# AdelinoR2.net
KiCad netlist of a schematic drawn in EAGLE
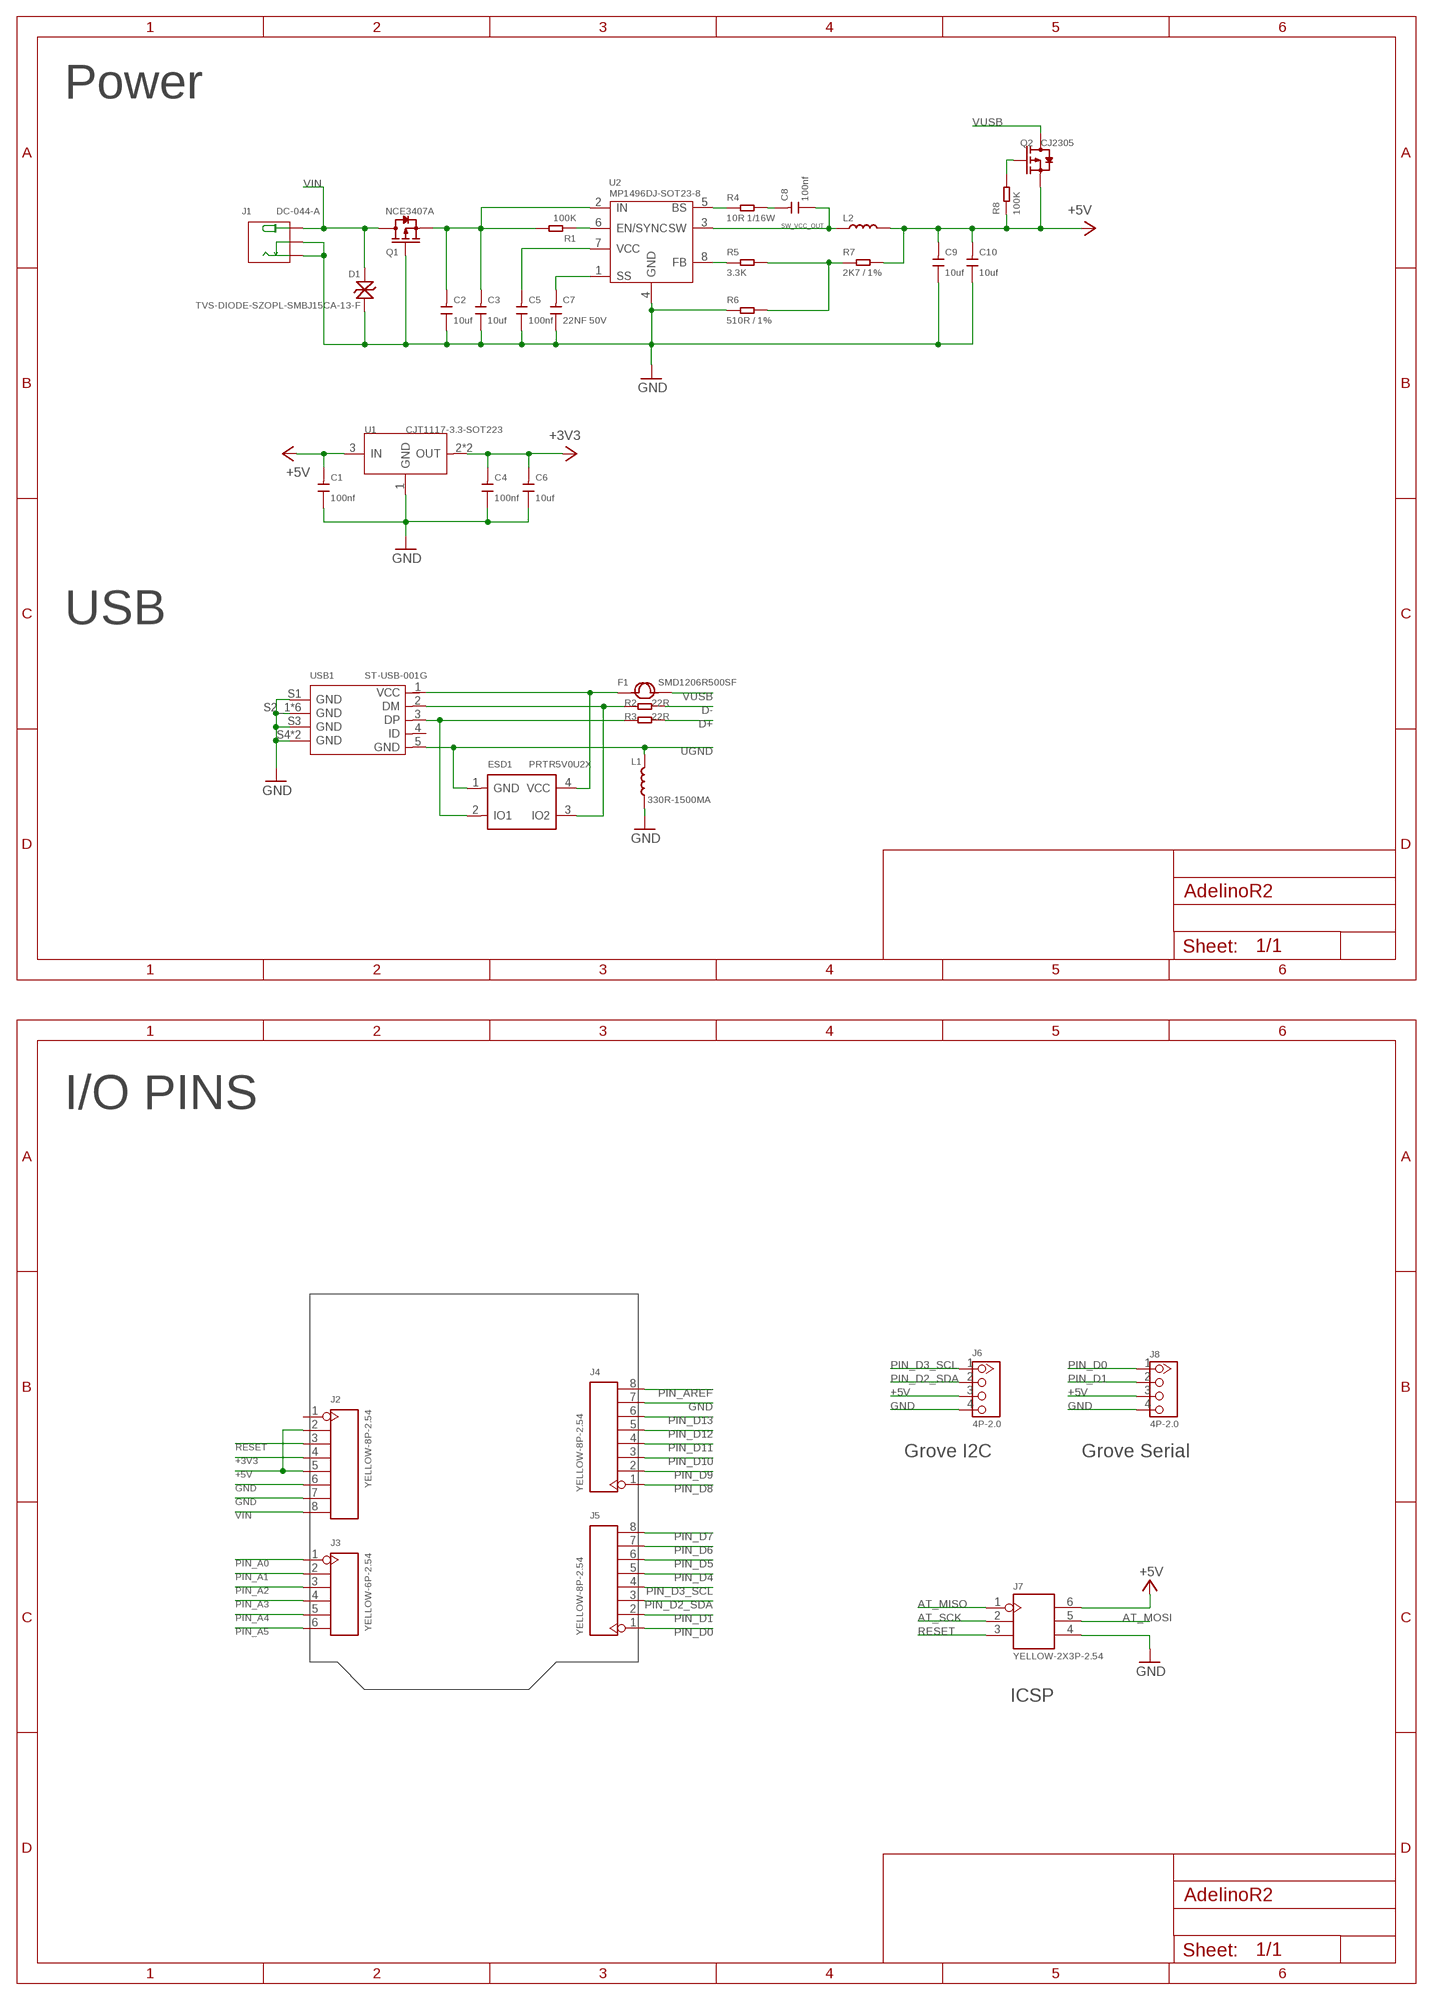
[diagram p0: schematic, sheet 1, part 1 of 2]
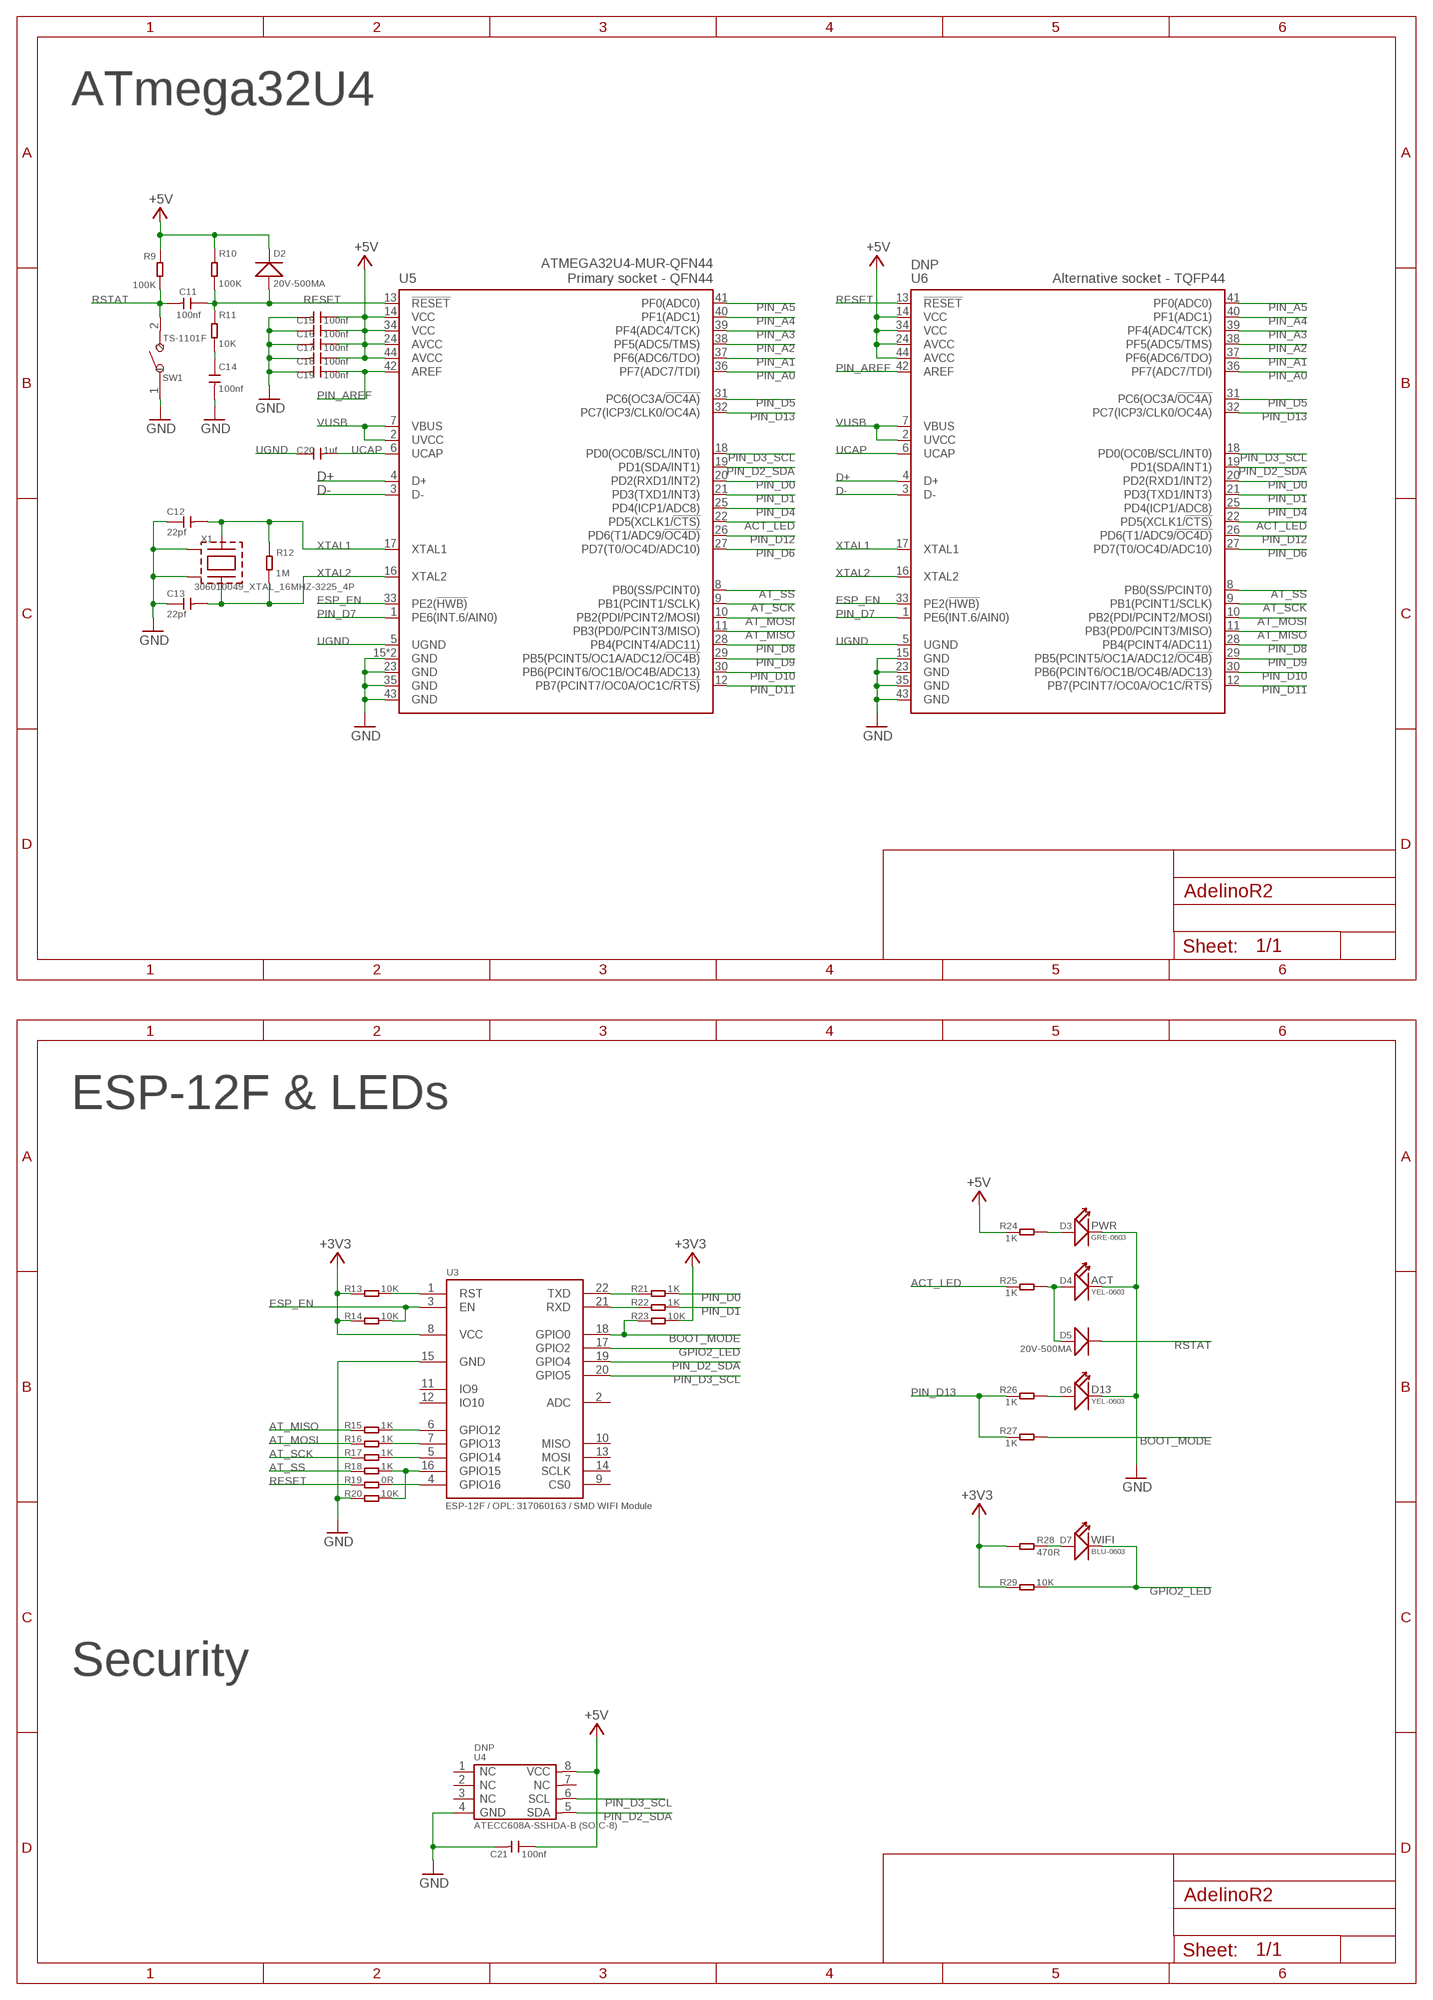
[diagram p1: schematic, sheet 1, part 2 of 2]

(export (version "E")
  (design (tool "Eeschema 10.0.6"))
  (components
    (comp (ref "C1")
      (value "100nf")
      (footprint "eagle-import:C0402")
      (fields (field (name "MPN") "CC0402KRX7R8BB104"))
      (libsource (lib "eagle-import") (part "CERAMIC-100NF-25V-10%-X7R(0402)"))
    )
    (comp (ref "C2")
      (value "10uf")
      (footprint "eagle-import:C0805")
      (fields (field (name "MPN") "CC0805KKX5R8BB106"))
      (libsource (lib "eagle-import") (part "CERAMIC-10UF-25V-10%-X5R(0805)"))
    )
    (comp (ref "C3")
      (value "10uf")
      (footprint "eagle-import:C0805")
      (fields (field (name "MPN") "CC0805KKX5R8BB106"))
      (libsource (lib "eagle-import") (part "CERAMIC-10UF-25V-10%-X5R(0805)"))
    )
    (comp (ref "C4")
      (value "100nf")
      (footprint "eagle-import:C0402")
      (fields (field (name "MPN") "CC0402KRX7R8BB104"))
      (libsource (lib "eagle-import") (part "CERAMIC-100NF-25V-10%-X7R(0402)"))
    )
    (comp (ref "C5")
      (value "100nf")
      (footprint "eagle-import:C0402")
      (fields (field (name "MPN") "CC0402KRX7R8BB104"))
      (libsource (lib "eagle-import") (part "CERAMIC-100NF-25V-10%-X7R(0402)"))
    )
    (comp (ref "C6")
      (value "10uf")
      (footprint "eagle-import:C0805")
      (fields (field (name "MPN") "CC0805KKX5R8BB106"))
      (libsource (lib "eagle-import") (part "CERAMIC-10UF-25V-10%-X5R(0805)"))
    )
    (comp (ref "C7")
      (value "22NF 50V")
      (footprint "eagle-import:C0402")
      (fields (field (name "MPN") "CC0402KRX7R9BB223"))
      (libsource (lib "eagle-import") (part "CERAMIC-22NF-50V-10%-X7R(0402)"))
    )
    (comp (ref "C8")
      (value "100nf")
      (footprint "eagle-import:C0402")
      (fields (field (name "MPN") "CC0402KRX7R8BB104"))
      (libsource (lib "eagle-import") (part "CERAMIC-100NF-25V-10%-X7R(0402)"))
    )
    (comp (ref "C9")
      (value "10uf")
      (footprint "eagle-import:C0805")
      (fields (field (name "MPN") "CC0805KKX5R8BB106"))
      (libsource (lib "eagle-import") (part "CERAMIC-10UF-25V-10%-X5R(0805)"))
    )
    (comp (ref "C10")
      (value "10uf")
      (footprint "eagle-import:C0805")
      (fields (field (name "MPN") "CC0805KKX5R8BB106"))
      (libsource (lib "eagle-import") (part "CERAMIC-10UF-25V-10%-X5R(0805)"))
    )
    (comp (ref "C11")
      (value "100nf")
      (footprint "eagle-import:C0402")
      (fields (field (name "MPN") "CC0402KRX7R8BB104"))
      (libsource (lib "eagle-import") (part "CERAMIC-100NF-25V-10%-X7R(0402)"))
    )
    (comp (ref "C12")
      (value "22pf")
      (footprint "eagle-import:C0402")
      (fields (field (name "MPN") "CC0402JRNPO9BN220"))
      (libsource (lib "eagle-import") (part "CERAMIC-22PF-50V-5%-NPO(0402)"))
    )
    (comp (ref "C13")
      (value "22pf")
      (footprint "eagle-import:C0402")
      (fields (field (name "MPN") "CC0402JRNPO9BN220"))
      (libsource (lib "eagle-import") (part "CERAMIC-22PF-50V-5%-NPO(0402)"))
    )
    (comp (ref "C14")
      (value "100nf")
      (footprint "eagle-import:C0402")
      (fields (field (name "MPN") "CC0402KRX7R8BB104"))
      (libsource (lib "eagle-import") (part "CERAMIC-100NF-25V-10%-X7R(0402)"))
    )
    (comp (ref "C15")
      (value "100nf")
      (footprint "eagle-import:C0402")
      (fields (field (name "MPN") "CC0402KRX7R8BB104"))
      (libsource (lib "eagle-import") (part "CERAMIC-100NF-25V-10%-X7R(0402)"))
    )
    (comp (ref "C16")
      (value "100nf")
      (footprint "eagle-import:C0402")
      (fields (field (name "MPN") "CC0402KRX7R8BB104"))
      (libsource (lib "eagle-import") (part "CERAMIC-100NF-25V-10%-X7R(0402)"))
    )
    (comp (ref "C17")
      (value "100nf")
      (footprint "eagle-import:C0402")
      (fields (field (name "MPN") "CC0402KRX7R8BB104"))
      (libsource (lib "eagle-import") (part "CERAMIC-100NF-25V-10%-X7R(0402)"))
    )
    (comp (ref "C18")
      (value "100nf")
      (footprint "eagle-import:C0402")
      (fields (field (name "MPN") "CC0402KRX7R8BB104"))
      (libsource (lib "eagle-import") (part "CERAMIC-100NF-25V-10%-X7R(0402)"))
    )
    (comp (ref "C19")
      (value "100nf")
      (footprint "eagle-import:C0402")
      (fields (field (name "MPN") "CC0402KRX7R8BB104"))
      (libsource (lib "eagle-import") (part "CERAMIC-100NF-25V-10%-X7R(0402)"))
    )
    (comp (ref "C20")
      (value "1uf")
      (footprint "eagle-import:C0805")
      (fields (field (name "MPN") "CC0805KKX7R8BB105"))
      (libsource (lib "eagle-import") (part "CERAMIC-1UF-25V-10%-X7R(0805)"))
    )
    (comp (ref "C21")
      (value "100nf")
      (footprint "eagle-import:C0402")
      (fields (field (name "MPN") "CC0402KRX7R8BB104"))
      (libsource (lib "eagle-import") (part "CERAMIC-100NF-25V-10%-X7R(0402)"))
    )
    (comp (ref "D1")
      (value "TVS-DIODE-SZOPL-SMBJ15CA-13-F")
      (footprint "eagle-import:DO-214AA")
      (fields (field (name "MPN") "SMBJ15CA-13-F"))
      (libsource (lib "eagle-import") (part "TVS-DIODE-SZOPL-SMBJ15CA-13-F"))
    )
    (comp (ref "D2")
      (value "20V-500MA")
      (footprint "eagle-import:SOD-123")
      (fields (field (name "MPN") "MBR0520LT1G"))
      (libsource (lib "eagle-import") (part "SMD-DIODE-SCHOTTKY-20V-500MA(SOD-123)P"))
    )
    (comp (ref "D3")
      (value "GRE-0603")
      (footprint "eagle-import:LED-0603")
      (fields (field (name "MPN") "19-217-G7C-AN1P2-3T") (field (name "LABEL") "PWR"))
      (libsource (lib "eagle-import") (part "SMD-LED-CLEAR-GREEN(0603)"))
    )
    (comp (ref "D4")
      (value "YEL-0603")
      (footprint "eagle-import:LED-0603")
      (fields (field (name "MPN") "19-217-Y5C-AM1N1VY-3T") (field (name "LABEL") "ACT"))
      (libsource (lib "eagle-import") (part "SMD-LED-CLEAR-YELLOW(0603)"))
    )
    (comp (ref "D5")
      (value "20V-500MA")
      (footprint "eagle-import:SOD-123")
      (fields (field (name "MPN") "MBR0520LT1G"))
      (libsource (lib "eagle-import") (part "SMD-DIODE-SCHOTTKY-20V-500MA(SOD-123)P"))
    )
    (comp (ref "D6")
      (value "YEL-0603")
      (footprint "eagle-import:LED-0603")
      (fields (field (name "MPN") "19-217-Y5C-AM1N1VY-3T") (field (name "LABEL") "D13"))
      (libsource (lib "eagle-import") (part "SMD-LED-CLEAR-YELLOW(0603)"))
    )
    (comp (ref "D7")
      (value "BLU-0603")
      (footprint "eagle-import:LED-0603")
      (fields (field (name "MPN") "19-217-BHC-ZL1M2RY-3T") (field (name "LABEL") "WIFI"))
      (libsource (lib "eagle-import") (part "SMD-LED-CLEAR-BLUE(0603)"))
    )
    (comp (ref "ESD1")
      (value "PRTR5V0U2X")
      (footprint "eagle-import:SOT-143B")
      (fields (field (name "MPN") "NXP;PRTR5V0U2X,215"))
      (libsource (lib "eagle-import") (part "SMD-DIODE-TVS-5.5V"))
    )
    (comp (ref "F1")
      (value "SMD1206R500SF")
      (footprint "eagle-import:F1206")
      (libsource (lib "eagle-import") (part "SMD-PPTC-500MA(1206)"))
    )
    (comp (ref "J1")
      (value "DC-044-A")
      (footprint "eagle-import:DCJ3P-11.6X9.6X7.0MM")
      (fields (field (name "MPN") "JACK-DC-044-A"))
      (libsource (lib "eagle-import") (part "JACK-DC-044-A"))
    )
    (comp (ref "J2")
      (value "YELLOW-8P-2.54")
      (footprint "eagle-import:H8-2.54")
      (fields (field (name "MPN") "F185-1108A1BSYC1"))
      (libsource (lib "eagle-import") (part "DIP-YELLOW-FEMALE-HEADER(8P-2.54)"))
    )
    (comp (ref "J3")
      (value "YELLOW-6P-2.54")
      (footprint "eagle-import:H6-2.54")
      (fields (field (name "MPN") "F185-1106A1BSYA3"))
      (libsource (lib "eagle-import") (part "DIP-YELLOW-FEMALE-HEADER-VERT(6P-2.54)"))
    )
    (comp (ref "J4")
      (value "YELLOW-8P-2.54")
      (footprint "eagle-import:H8-2.54")
      (fields (field (name "MPN") "F185-1108A1BSYC1"))
      (libsource (lib "eagle-import") (part "DIP-YELLOW-FEMALE-HEADER(8P-2.54)"))
    )
    (comp (ref "J5")
      (value "YELLOW-8P-2.54")
      (footprint "eagle-import:H8-2.54")
      (fields (field (name "MPN") "F185-1108A1BSYC1"))
      (libsource (lib "eagle-import") (part "DIP-YELLOW-FEMALE-HEADER(8P-2.54)"))
    )
    (comp (ref "J6")
      (value "4P-2.0")
      (footprint "eagle-import:HW4-2.0")
      (libsource (lib "eagle-import") (part "GROVE-CONNECTOR-DIP(4P-2.0)"))
    )
    (comp (ref "J7")
      (value "YELLOW-2X3P-2.54")
      (footprint "eagle-import:H2X3-2.54")
      (fields (field (name "MPN") "P125-1203A0BS116A2"))
      (libsource (lib "eagle-import") (part "DIP-YELLOW-MALE-HEADER-VERT(2X3P-2.54)"))
    )
    (comp (ref "J8")
      (value "4P-2.0")
      (footprint "eagle-import:HW4-2.0")
      (libsource (lib "eagle-import") (part "GROVE-CONNECTOR-DIP(4P-2.0)"))
    )
    (comp (ref "L1")
      (value "330R-1500MA")
      (footprint "eagle-import:L0805")
      (fields (field (name "MPN") "BLM21PG331SN1D"))
      (libsource (lib "eagle-import") (part "SMD-FERRITE-BEAD-330R-1500MA(0805)'0805'"))
    )
    (comp (ref "L2")
      (value "10UH-225MA")
      (footprint "eagle-import:L5040S")
      (libsource (lib "eagle-import") (part "SMD-INDUCTOR-10UH-20%-2.35A(2P-5X5X4MM)"))
    )
    (comp (ref "Q1")
      (value "NCE3407A")
      (footprint "eagle-import:SOT-23")
      (libsource (lib "eagle-import") (part "SMD-MOSFET-P-CH-VDC=30V-ID=4.3A-NCE3407A(SOT-23)"))
    )
    (comp (ref "Q2")
      (value "CJ2305")
      (footprint "eagle-import:SOT-23")
      (libsource (lib "eagle-import") (part "SMD-MOSFET-P-CH-8V-4.1A-CJ2305(SOT-23)"))
    )
    (comp (ref "R1")
      (value "100K")
      (footprint "eagle-import:R0402")
      (fields (field (name "MPN") "RC0402FR-07100KL"))
      (libsource (lib "eagle-import") (part "SMD-RES-100K-1%-1/16W(0402)"))
    )
    (comp (ref "R2")
      (value "22R")
      (footprint "eagle-import:R0402")
      (fields (field (name "MPN") "RC0402FR-0722RL"))
      (libsource (lib "eagle-import") (part "SMD-RES-22R-1%-1/16W(0402)"))
    )
    (comp (ref "R3")
      (value "22R")
      (footprint "eagle-import:R0402")
      (fields (field (name "MPN") "RC0402FR-0722RL"))
      (libsource (lib "eagle-import") (part "SMD-RES-22R-1%-1/16W(0402)"))
    )
    (comp (ref "R4")
      (value "10R 1/16W")
      (footprint "eagle-import:R0402")
      (fields (field (name "MPN") "RC0402FR-0710RL"))
      (libsource (lib "eagle-import") (part "SMD-RES-10R-1%-1/16W(0402)"))
    )
    (comp (ref "R5")
      (value "3.3K")
      (footprint "eagle-import:R0402")
      (fields (field (name "MPN") "RC0402JR-073K3L"))
      (libsource (lib "eagle-import") (part "SMD-RES-3.3K-5%-1/16W(0402)"))
    )
    (comp (ref "R6")
      (value "3K / 1%")
      (footprint "eagle-import:R0603")
      (fields (field (name "R") "510R / 1%"))
      (libsource (lib "eagle-import") (part "SMD-RES-510R-1%-1/10W(0603)"))
    )
    (comp (ref "R7")
      (value "2K7 / 1%")
      (footprint "eagle-import:R0603")
      (fields (field (name "R") "2K7 / 1%"))
      (libsource (lib "eagle-import") (part "SMD-RES-2.7K-1%-1/10W(0603)"))
    )
    (comp (ref "R8")
      (value "100K")
      (footprint "eagle-import:R0402")
      (fields (field (name "MPN") "RC0402FR-07100KL"))
      (libsource (lib "eagle-import") (part "SMD-RES-100K-1%-1/16W(0402)"))
    )
    (comp (ref "R9")
      (value "100K")
      (footprint "eagle-import:R0402")
      (fields (field (name "MPN") "RC0402FR-07100KL"))
      (libsource (lib "eagle-import") (part "SMD-RES-100K-1%-1/16W(0402)"))
    )
    (comp (ref "R10")
      (value "100K")
      (footprint "eagle-import:R0402")
      (fields (field (name "MPN") "RC0402FR-07100KL"))
      (libsource (lib "eagle-import") (part "SMD-RES-100K-1%-1/16W(0402)"))
    )
    (comp (ref "R11")
      (value "10K")
      (footprint "eagle-import:R0402")
      (fields (field (name "MPN") "RC0402FR-0710KL"))
      (libsource (lib "eagle-import") (part "SMD-RES-10K-1%-1/16W(0402)"))
    )
    (comp (ref "R12")
      (value "1M")
      (footprint "eagle-import:R0402")
      (fields (field (name "MPN") "RC0402FR-071ML"))
      (libsource (lib "eagle-import") (part "SMD-RES-1M-1%-1/16W(0402)"))
    )
    (comp (ref "R13")
      (value "10K")
      (footprint "eagle-import:R0402")
      (fields (field (name "MPN") "RC0402FR-0710KL"))
      (libsource (lib "eagle-import") (part "SMD-RES-10K-1%-1/16W(0402)"))
    )
    (comp (ref "R14")
      (value "10K")
      (footprint "eagle-import:R0402")
      (fields (field (name "MPN") "RC0402FR-0710KL"))
      (libsource (lib "eagle-import") (part "SMD-RES-10K-1%-1/16W(0402)"))
    )
    (comp (ref "R15")
      (value "1K")
      (footprint "eagle-import:R0402")
      (fields (field (name "MPN") "RC0402JR-071KL"))
      (libsource (lib "eagle-import") (part "SMD-RES-1K-5%-1/16W(0402)"))
    )
    (comp (ref "R16")
      (value "1K")
      (footprint "eagle-import:R0402")
      (fields (field (name "MPN") "RC0402JR-071KL"))
      (libsource (lib "eagle-import") (part "SMD-RES-1K-5%-1/16W(0402)"))
    )
    (comp (ref "R17")
      (value "1K")
      (footprint "eagle-import:R0402")
      (fields (field (name "MPN") "RC0402JR-071KL"))
      (libsource (lib "eagle-import") (part "SMD-RES-1K-5%-1/16W(0402)"))
    )
    (comp (ref "R18")
      (value "1K")
      (footprint "eagle-import:R0402")
      (fields (field (name "MPN") "RC0402JR-071KL"))
      (libsource (lib "eagle-import") (part "SMD-RES-1K-5%-1/16W(0402)"))
    )
    (comp (ref "R19")
      (value "0R")
      (footprint "eagle-import:R0402")
      (fields (field (name "MPN") "RC0402JR-070RL"))
      (libsource (lib "eagle-import") (part "SMD-RES-0R-5%-1/16W(0402)"))
    )
    (comp (ref "R20")
      (value "10K")
      (footprint "eagle-import:R0402")
      (fields (field (name "MPN") "RC0402FR-0710KL"))
      (libsource (lib "eagle-import") (part "SMD-RES-10K-1%-1/16W(0402)"))
    )
    (comp (ref "R21")
      (value "1K")
      (footprint "eagle-import:R0402")
      (fields (field (name "MPN") "RC0402JR-071KL"))
      (libsource (lib "eagle-import") (part "SMD-RES-1K-5%-1/16W(0402)"))
    )
    (comp (ref "R22")
      (value "1K")
      (footprint "eagle-import:R0402")
      (fields (field (name "MPN") "RC0402JR-071KL"))
      (libsource (lib "eagle-import") (part "SMD-RES-1K-5%-1/16W(0402)"))
    )
    (comp (ref "R23")
      (value "10K")
      (footprint "eagle-import:R0402")
      (fields (field (name "MPN") "RC0402FR-0710KL"))
      (libsource (lib "eagle-import") (part "SMD-RES-10K-1%-1/16W(0402)"))
    )
    (comp (ref "R24")
      (value "1K")
      (footprint "eagle-import:R0402")
      (fields (field (name "MPN") "RC0402JR-071KL"))
      (libsource (lib "eagle-import") (part "SMD-RES-1K-5%-1/16W(0402)"))
    )
    (comp (ref "R25")
      (value "1K")
      (footprint "eagle-import:R0402")
      (fields (field (name "MPN") "RC0402JR-071KL"))
      (libsource (lib "eagle-import") (part "SMD-RES-1K-5%-1/16W(0402)"))
    )
    (comp (ref "R26")
      (value "1K")
      (footprint "eagle-import:R0402")
      (fields (field (name "MPN") "RC0402JR-071KL"))
      (libsource (lib "eagle-import") (part "SMD-RES-1K-5%-1/16W(0402)"))
    )
    (comp (ref "R27")
      (value "1K")
      (footprint "eagle-import:R0402")
      (fields (field (name "MPN") "RC0402JR-071KL"))
      (libsource (lib "eagle-import") (part "SMD-RES-1K-5%-1/16W(0402)"))
    )
    (comp (ref "R28")
      (value "470R")
      (footprint "eagle-import:R0402")
      (fields (field (name "MPN") "RC0402JR-07470RL"))
      (libsource (lib "eagle-import") (part "SMD-RES-470R-5%-1/16W(0402)"))
    )
    (comp (ref "R29")
      (value "10K")
      (footprint "eagle-import:R0402")
      (fields (field (name "MPN") "RC0402FR-0710KL"))
      (libsource (lib "eagle-import") (part "SMD-RES-10K-1%-1/16W(0402)"))
    )
    (comp (ref "SW1")
      (value "TS-1101F")
      (footprint "eagle-import:SW2-5.0-6.0X3.0X4.3MM")
      (libsource (lib "eagle-import") (part "DIP-BUTTON(2P-6.0X3.0X4.3MM)-TS-1101F"))
    )
    (comp (ref "U1")
      (value "CJT1117-3.3-SOT223")
      (footprint "eagle-import:SOT-223")
      (fields (field (name "MPN") "CJT1117-3.3"))
      (libsource (lib "eagle-import") (part "PMIC-CJT1117-3.3(SOT223)"))
    )
    (comp (ref "U2")
      (value "MP1496DJ-SOT23-8")
      (footprint "eagle-import:SOT-23-8")
      (fields (field (name "MPN") "MP1496DJ"))
      (libsource (lib "eagle-import") (part "PMIC-MP1496DJ(SOT23-8)"))
    )
    (comp (ref "U3")
      (value "ESP-12F / OPL: 317060163 / SMD WIFI Module")
      (footprint "eagle-import:ESP-12F")
      (libsource (lib "eagle-import") (part "ESP-12F"))
    )
    (comp (ref "U4")
      (value "DNP")
      (footprint "eagle-import:SOIC8-1.27-5X4MM")
      (fields
        (field (name "MPN") "ATECC608")
        (field (name "DESC") "ATECC608A-SSHDA-B (SOIC-8)")
        (field (name "MPN_1") "ATECC608A-SSHDA-B")
      )
      (libsource (lib "eagle-import") (part "ATECC608(SOIC8)"))
    )
    (comp (ref "U5")
      (value "ATMEGA32U4-MUR-QFN44")
      (footprint "eagle-import:QFN44G-0.5-7X7MM")
      (fields (field (name "MPN") "ATMEGA32U4-MUR") (field (name "DESC") "Primary socket - QFN44"))
      (libsource (lib "eagle-import") (part "MCU-ATMEGA32U4-MUR(VQFN44)"))
    )
    (comp (ref "U6")
      (value "DNP")
      (footprint "eagle-import:TQFP44-0.8-9.6X9.6MM")
      (fields (field (name "MPN") "ATMEGA32U4") (field (name "DESC") "Alternative socket - TQFP44"))
      (libsource (lib "eagle-import") (part "MCU-ATMEGA32U4-AU(TQFP44)"))
    )
    (comp (ref "USB1")
      (value "ST-USB-001G")
      (footprint "eagle-import:MICRO-USB5+4P-SMD-0.65-B")
      (libsource (lib "eagle-import") (part "MICRO-USB-SMD-B-WITHOUT-POST-W/P(ST-USB-001G)"))
    )
    (comp (ref "X1")
      (value "306010049_XTAL_16MHZ-3225_4P")
      (footprint "eagle-import:X3225_4P")
      (libsource (lib "eagle-import") (part "306010049_XTAL_16MHZ-3225_4P"))
    )
  )
  (nets
    (net (code "1") (name "+3V3") (class "Default")
      (node (ref "C4") (pin "2") (pinfunction "2_2") (pintype "passive"))
      (node (ref "C6") (pin "2") (pinfunction "2_2") (pintype "passive"))
      (node (ref "J2") (pin "4") (pinfunction "4_4") (pintype "bidirectional"))
      (node (ref "R13") (pin "1") (pinfunction "1_1") (pintype "passive"))
      (node (ref "R14") (pin "1") (pinfunction "1_1") (pintype "passive"))
      (node (ref "R23") (pin "2") (pinfunction "2_2") (pintype "passive"))
      (node (ref "R28") (pin "1") (pinfunction "1_1") (pintype "passive"))
      (node (ref "R29") (pin "1") (pinfunction "1_1") (pintype "passive"))
      (node (ref "U1") (pin "2") (pinfunction "OUT_2") (pintype "bidirectional"))
      (node (ref "U1") (pin "TER") (pinfunction "OUT_TER") (pintype "bidirectional"))
      (node (ref "U3") (pin "8") (pinfunction "VCC_8") (pintype "bidirectional"))
    )
    (net (code "2") (name "+5V") (class "Default")
      (node (ref "C1") (pin "2") (pinfunction "2_2") (pintype "passive"))
      (node (ref "C10") (pin "2") (pinfunction "2_2") (pintype "passive"))
      (node (ref "C15") (pin "1") (pinfunction "1_1") (pintype "passive"))
      (node (ref "C16") (pin "1") (pinfunction "1_1") (pintype "passive"))
      (node (ref "C17") (pin "1") (pinfunction "1_1") (pintype "passive"))
      (node (ref "C18") (pin "1") (pinfunction "1_1") (pintype "passive"))
      (node (ref "C21") (pin "1") (pinfunction "1_1") (pintype "passive"))
      (node (ref "C9") (pin "2") (pinfunction "2_2") (pintype "passive"))
      (node (ref "D2") (pin "-") (pinfunction "-_-") (pintype "passive"))
      (node (ref "J2") (pin "2") (pinfunction "2_2") (pintype "bidirectional"))
      (node (ref "J2") (pin "5") (pinfunction "5_5") (pintype "bidirectional"))
      (node (ref "J6") (pin "3") (pinfunction "3_3") (pintype "bidirectional"))
      (node (ref "J7") (pin "6") (pinfunction "6_6") (pintype "bidirectional"))
      (node (ref "J8") (pin "3") (pinfunction "3_3") (pintype "bidirectional"))
      (node (ref "L2") (pin "2") (pinfunction "2_2") (pintype "passive"))
      (node (ref "Q2") (pin "2") (pinfunction "S_2") (pintype "passive"))
      (node (ref "R10") (pin "2") (pinfunction "2_2") (pintype "passive"))
      (node (ref "R24") (pin "1") (pinfunction "1_1") (pintype "passive"))
      (node (ref "R7") (pin "2") (pinfunction "2_2") (pintype "passive"))
      (node (ref "R8") (pin "1") (pinfunction "1_1") (pintype "passive"))
      (node (ref "R9") (pin "1") (pinfunction "1_1") (pintype "passive"))
      (node (ref "U1") (pin "3") (pinfunction "IN_3") (pintype "bidirectional"))
      (node (ref "U4") (pin "8") (pinfunction "VCC_8") (pintype "power_in"))
      (node (ref "U5") (pin "14") (pinfunction "VCC_14") (pintype "bidirectional"))
      (node (ref "U5") (pin "24") (pinfunction "AVCC_24") (pintype "bidirectional"))
      (node (ref "U5") (pin "34") (pinfunction "VCC_34") (pintype "bidirectional"))
      (node (ref "U5") (pin "44") (pinfunction "AVCC_44") (pintype "bidirectional"))
      (node (ref "U6") (pin "14") (pinfunction "VCC_14") (pintype "bidirectional"))
      (node (ref "U6") (pin "24") (pinfunction "AVCC_24") (pintype "bidirectional"))
      (node (ref "U6") (pin "34") (pinfunction "VCC_34") (pintype "bidirectional"))
      (node (ref "U6") (pin "44") (pinfunction "AVCC_44") (pintype "bidirectional"))
    )
    (net (code "3") (name "/ACT_LED") (class "Default")
      (node (ref "R25") (pin "1") (pinfunction "1_1") (pintype "passive"))
      (node (ref "U5") (pin "22") (pinfunction "PD5(XCLK1/~{CTS})_22") (pintype "bidirectional"))
      (node (ref "U6") (pin "22") (pinfunction "PD5(XCLK1/~{CTS})_22") (pintype "bidirectional"))
    )
    (net (code "4") (name "/AT_MISO") (class "Default")
      (node (ref "J7") (pin "1") (pinfunction "1_1") (pintype "bidirectional"))
      (node (ref "R15") (pin "1") (pinfunction "1_1") (pintype "passive"))
      (node (ref "U5") (pin "11") (pinfunction "PB3(PD0/PCINT3/MISO)_11") (pintype "bidirectional"))
      (node (ref "U6") (pin "11") (pinfunction "PB3(PD0/PCINT3/MISO)_11") (pintype "bidirectional"))
    )
    (net (code "5") (name "/AT_MOSI") (class "Default")
      (node (ref "J7") (pin "5") (pinfunction "5_5") (pintype "bidirectional"))
      (node (ref "R16") (pin "1") (pinfunction "1_1") (pintype "passive"))
      (node (ref "U5") (pin "10") (pinfunction "PB2(PDI/PCINT2/MOSI)_10") (pintype "bidirectional"))
      (node (ref "U6") (pin "10") (pinfunction "PB2(PDI/PCINT2/MOSI)_10") (pintype "bidirectional"))
    )
    (net (code "6") (name "/AT_SCK") (class "Default")
      (node (ref "J7") (pin "2") (pinfunction "2_2") (pintype "bidirectional"))
      (node (ref "R17") (pin "1") (pinfunction "1_1") (pintype "passive"))
      (node (ref "U5") (pin "9") (pinfunction "PB1(PCINT1/SCLK)_9") (pintype "bidirectional"))
      (node (ref "U6") (pin "9") (pinfunction "PB1(PCINT1/SCLK)_9") (pintype "bidirectional"))
    )
    (net (code "7") (name "/AT_SS") (class "Default")
      (node (ref "R18") (pin "1") (pinfunction "1_1") (pintype "passive"))
      (node (ref "U5") (pin "8") (pinfunction "PB0(SS/PCINT0)_8") (pintype "bidirectional"))
      (node (ref "U6") (pin "8") (pinfunction "PB0(SS/PCINT0)_8") (pintype "bidirectional"))
    )
    (net (code "8") (name "/BOOT_MODE") (class "Default")
      (node (ref "R23") (pin "1") (pinfunction "1_1") (pintype "passive"))
      (node (ref "R27") (pin "2") (pinfunction "2_2") (pintype "passive"))
      (node (ref "U3") (pin "18") (pinfunction "GPIO0_18") (pintype "bidirectional"))
    )
    (net (code "9") (name "/D+") (class "Default")
      (node (ref "R3") (pin "2") (pinfunction "2_2") (pintype "passive"))
      (node (ref "U5") (pin "4") (pinfunction "D+_4") (pintype "bidirectional"))
      (node (ref "U6") (pin "4") (pinfunction "D+_4") (pintype "bidirectional"))
    )
    (net (code "10") (name "/D-") (class "Default")
      (node (ref "R2") (pin "2") (pinfunction "2_2") (pintype "passive"))
      (node (ref "U5") (pin "3") (pinfunction "D-_3") (pintype "bidirectional"))
      (node (ref "U6") (pin "3") (pinfunction "D-_3") (pintype "bidirectional"))
    )
    (net (code "11") (name "/ESP_EN") (class "Default")
      (node (ref "R14") (pin "2") (pinfunction "2_2") (pintype "passive"))
      (node (ref "U3") (pin "3") (pinfunction "EN_3") (pintype "bidirectional"))
      (node (ref "U5") (pin "33") (pinfunction "PE2(~{HWB})_33") (pintype "bidirectional"))
      (node (ref "U6") (pin "33") (pinfunction "PE2(~{HWB})_33") (pintype "bidirectional"))
    )
    (net (code "12") (name "/GPIO2_LED") (class "Default")
      (node (ref "D7") (pin "-") (pinfunction "-_-") (pintype "passive"))
      (node (ref "R29") (pin "2") (pinfunction "2_2") (pintype "passive"))
      (node (ref "U3") (pin "17") (pinfunction "GPIO2_17") (pintype "bidirectional"))
    )
    (net (code "13") (name "/PIN_A0") (class "Default")
      (node (ref "J3") (pin "1") (pinfunction "1_1") (pintype "bidirectional"))
      (node (ref "U5") (pin "36") (pinfunction "PF7(ADC7/TDI)_36") (pintype "bidirectional"))
      (node (ref "U6") (pin "36") (pinfunction "PF7(ADC7/TDI)_36") (pintype "bidirectional"))
    )
    (net (code "14") (name "/PIN_A1") (class "Default")
      (node (ref "J3") (pin "2") (pinfunction "2_2") (pintype "bidirectional"))
      (node (ref "U5") (pin "37") (pinfunction "PF6(ADC6/TDO)_37") (pintype "bidirectional"))
      (node (ref "U6") (pin "37") (pinfunction "PF6(ADC6/TDO)_37") (pintype "bidirectional"))
    )
    (net (code "15") (name "/PIN_A2") (class "Default")
      (node (ref "J3") (pin "3") (pinfunction "3_3") (pintype "bidirectional"))
      (node (ref "U5") (pin "38") (pinfunction "PF5(ADC5/TMS)_38") (pintype "bidirectional"))
      (node (ref "U6") (pin "38") (pinfunction "PF5(ADC5/TMS)_38") (pintype "bidirectional"))
    )
    (net (code "16") (name "/PIN_A3") (class "Default")
      (node (ref "J3") (pin "4") (pinfunction "4_4") (pintype "bidirectional"))
      (node (ref "U5") (pin "39") (pinfunction "PF4(ADC4/TCK)_39") (pintype "bidirectional"))
      (node (ref "U6") (pin "39") (pinfunction "PF4(ADC4/TCK)_39") (pintype "bidirectional"))
    )
    (net (code "17") (name "/PIN_A4") (class "Default")
      (node (ref "J3") (pin "5") (pinfunction "5_5") (pintype "bidirectional"))
      (node (ref "U5") (pin "40") (pinfunction "PF1(ADC1)_40") (pintype "bidirectional"))
      (node (ref "U6") (pin "40") (pinfunction "PF1(ADC1)_40") (pintype "bidirectional"))
    )
    (net (code "18") (name "/PIN_A5") (class "Default")
      (node (ref "J3") (pin "6") (pinfunction "6_6") (pintype "bidirectional"))
      (node (ref "U5") (pin "41") (pinfunction "PF0(ADC0)_41") (pintype "bidirectional"))
      (node (ref "U6") (pin "41") (pinfunction "PF0(ADC0)_41") (pintype "bidirectional"))
    )
    (net (code "19") (name "/PIN_AREF") (class "Default")
      (node (ref "C19") (pin "1") (pinfunction "1_1") (pintype "passive"))
      (node (ref "J4") (pin "8") (pinfunction "8_8") (pintype "bidirectional"))
      (node (ref "U5") (pin "42") (pinfunction "AREF_42") (pintype "bidirectional"))
      (node (ref "U6") (pin "42") (pinfunction "AREF_42") (pintype "bidirectional"))
    )
    (net (code "20") (name "/PIN_D0") (class "Default")
      (node (ref "J5") (pin "1") (pinfunction "1_1") (pintype "bidirectional"))
      (node (ref "J8") (pin "1") (pinfunction "1_1") (pintype "bidirectional"))
      (node (ref "R21") (pin "2") (pinfunction "2_2") (pintype "passive"))
      (node (ref "U5") (pin "20") (pinfunction "PD2(RXD1/INT2)_20") (pintype "bidirectional"))
      (node (ref "U6") (pin "20") (pinfunction "PD2(RXD1/INT2)_20") (pintype "bidirectional"))
    )
    (net (code "21") (name "/PIN_D1") (class "Default")
      (node (ref "J5") (pin "2") (pinfunction "2_2") (pintype "bidirectional"))
      (node (ref "J8") (pin "2") (pinfunction "2_2") (pintype "bidirectional"))
      (node (ref "R22") (pin "2") (pinfunction "2_2") (pintype "passive"))
      (node (ref "U5") (pin "21") (pinfunction "PD3(TXD1/INT3)_21") (pintype "bidirectional"))
      (node (ref "U6") (pin "21") (pinfunction "PD3(TXD1/INT3)_21") (pintype "bidirectional"))
    )
    (net (code "22") (name "/PIN_D2_SDA") (class "Default")
      (node (ref "J5") (pin "3") (pinfunction "3_3") (pintype "bidirectional"))
      (node (ref "J6") (pin "2") (pinfunction "2_2") (pintype "bidirectional"))
      (node (ref "U3") (pin "19") (pinfunction "GPIO4_19") (pintype "bidirectional"))
      (node (ref "U4") (pin "5") (pinfunction "SDA_5") (pintype "bidirectional"))
      (node (ref "U5") (pin "19") (pinfunction "PD1(SDA/INT1)_19") (pintype "bidirectional"))
      (node (ref "U6") (pin "19") (pinfunction "PD1(SDA/INT1)_19") (pintype "bidirectional"))
    )
    (net (code "23") (name "/PIN_D3_SCL") (class "Default")
      (node (ref "J5") (pin "4") (pinfunction "4_4") (pintype "bidirectional"))
      (node (ref "J6") (pin "1") (pinfunction "1_1") (pintype "bidirectional"))
      (node (ref "U3") (pin "20") (pinfunction "GPIO5_20") (pintype "bidirectional"))
      (node (ref "U4") (pin "6") (pinfunction "SCL_6") (pintype "input"))
      (node (ref "U5") (pin "18") (pinfunction "PD0(OC0B/SCL/INT0)_18") (pintype "bidirectional"))
      (node (ref "U6") (pin "18") (pinfunction "PD0(OC0B/SCL/INT0)_18") (pintype "bidirectional"))
    )
    (net (code "24") (name "/PIN_D4") (class "Default")
      (node (ref "J5") (pin "5") (pinfunction "5_5") (pintype "bidirectional"))
      (node (ref "U5") (pin "25") (pinfunction "PD4(ICP1/ADC8)_25") (pintype "bidirectional"))
      (node (ref "U6") (pin "25") (pinfunction "PD4(ICP1/ADC8)_25") (pintype "bidirectional"))
    )
    (net (code "25") (name "/PIN_D5") (class "Default")
      (node (ref "J5") (pin "6") (pinfunction "6_6") (pintype "bidirectional"))
      (node (ref "U5") (pin "31") (pinfunction "PC6(OC3A/~{OC4A})_31") (pintype "bidirectional"))
      (node (ref "U6") (pin "31") (pinfunction "PC6(OC3A/~{OC4A})_31") (pintype "bidirectional"))
    )
    (net (code "26") (name "/PIN_D6") (class "Default")
      (node (ref "J5") (pin "7") (pinfunction "7_7") (pintype "bidirectional"))
      (node (ref "U5") (pin "27") (pinfunction "PD7(T0/OC4D/ADC10)_27") (pintype "bidirectional"))
      (node (ref "U6") (pin "27") (pinfunction "PD7(T0/OC4D/ADC10)_27") (pintype "bidirectional"))
    )
    (net (code "27") (name "/PIN_D7") (class "Default")
      (node (ref "J5") (pin "8") (pinfunction "8_8") (pintype "bidirectional"))
      (node (ref "U5") (pin "1") (pinfunction "PE6(INT.6/AIN0)_1") (pintype "bidirectional"))
      (node (ref "U6") (pin "1") (pinfunction "PE6(INT.6/AIN0)_1") (pintype "bidirectional"))
    )
    (net (code "28") (name "/PIN_D8") (class "Default")
      (node (ref "J4") (pin "1") (pinfunction "1_1") (pintype "bidirectional"))
      (node (ref "U5") (pin "28") (pinfunction "PB4(PCINT4/ADC11)_28") (pintype "bidirectional"))
      (node (ref "U6") (pin "28") (pinfunction "PB4(PCINT4/ADC11)_28") (pintype "bidirectional"))
    )
    (net (code "29") (name "/PIN_D9") (class "Default")
      (node (ref "J4") (pin "2") (pinfunction "2_2") (pintype "bidirectional"))
      (node (ref "U5") (pin "29") (pinfunction "PB5(PCINT5/OC1A/ADC12/~{OC4B})_29") (pintype "bidirectional"))
      (node (ref "U6") (pin "29") (pinfunction "PB5(PCINT5/OC1A/ADC12/~{OC4B})_29") (pintype "bidirectional"))
    )
    (net (code "30") (name "/PIN_D10") (class "Default")
      (node (ref "J4") (pin "3") (pinfunction "3_3") (pintype "bidirectional"))
      (node (ref "U5") (pin "30") (pinfunction "PB6(PCINT6/OC1B/OC4B/ADC13)_30") (pintype "bidirectional"))
      (node (ref "U6") (pin "30") (pinfunction "PB6(PCINT6/OC1B/OC4B/ADC13)_30") (pintype "bidirectional"))
    )
    (net (code "31") (name "/PIN_D11") (class "Default")
      (node (ref "J4") (pin "4") (pinfunction "4_4") (pintype "bidirectional"))
      (node (ref "U5") (pin "12") (pinfunction "PB7(PCINT7/OC0A/OC1C/~{RTS})_12") (pintype "bidirectional"))
      (node (ref "U6") (pin "12") (pinfunction "PB7(PCINT7/OC0A/OC1C/~{RTS})_12") (pintype "bidirectional"))
    )
    (net (code "32") (name "/PIN_D12") (class "Default")
      (node (ref "J4") (pin "5") (pinfunction "5_5") (pintype "bidirectional"))
      (node (ref "U5") (pin "26") (pinfunction "PD6(T1/ADC9/~{OC4D})_26") (pintype "bidirectional"))
      (node (ref "U6") (pin "26") (pinfunction "PD6(T1/ADC9/~{OC4D})_26") (pintype "bidirectional"))
    )
    (net (code "33") (name "/PIN_D13") (class "Default")
      (node (ref "J4") (pin "6") (pinfunction "6_6") (pintype "bidirectional"))
      (node (ref "R26") (pin "1") (pinfunction "1_1") (pintype "passive"))
      (node (ref "R27") (pin "1") (pinfunction "1_1") (pintype "passive"))
      (node (ref "U5") (pin "32") (pinfunction "PC7(ICP3/CLK0/OC4A)_32") (pintype "bidirectional"))
      (node (ref "U6") (pin "32") (pinfunction "PC7(ICP3/CLK0/OC4A)_32") (pintype "bidirectional"))
    )
    (net (code "34") (name "/RESET") (class "Default")
      (node (ref "C11") (pin "1") (pinfunction "1_1") (pintype "passive"))
      (node (ref "D2") (pin "+") (pinfunction "+_+") (pintype "passive"))
      (node (ref "J2") (pin "3") (pinfunction "3_3") (pintype "bidirectional"))
      (node (ref "J7") (pin "3") (pinfunction "3_3") (pintype "bidirectional"))
      (node (ref "R10") (pin "1") (pinfunction "1_1") (pintype "passive"))
      (node (ref "R11") (pin "1") (pinfunction "1_1") (pintype "passive"))
      (node (ref "R19") (pin "1") (pinfunction "1_1") (pintype "passive"))
      (node (ref "U5") (pin "13") (pinfunction "~{RESET}_13") (pintype "bidirectional"))
      (node (ref "U6") (pin "13") (pinfunction "~{RESET}_13") (pintype "bidirectional"))
    )
    (net (code "35") (name "/RSTAT") (class "Default")
      (node (ref "C11") (pin "2") (pinfunction "2_2") (pintype "passive"))
      (node (ref "D5") (pin "-") (pinfunction "-_-") (pintype "passive"))
      (node (ref "R9") (pin "2") (pinfunction "2_2") (pintype "passive"))
      (node (ref "SW1") (pin "2") (pinfunction "2_2") (pintype "bidirectional"))
    )
    (net (code "36") (name "/SW_VCC_OUT") (class "Default")
      (node (ref "C8") (pin "1") (pinfunction "1_1") (pintype "passive"))
      (node (ref "L2") (pin "1") (pinfunction "1_1") (pintype "passive"))
      (node (ref "U2") (pin "3") (pinfunction "SW_3") (pintype "bidirectional"))
    )
    (net (code "37") (name "/UCAP") (class "Default")
      (node (ref "C20") (pin "2") (pinfunction "2_2") (pintype "passive"))
      (node (ref "U5") (pin "6") (pinfunction "UCAP_6") (pintype "bidirectional"))
      (node (ref "U6") (pin "6") (pinfunction "UCAP_6") (pintype "bidirectional"))
    )
    (net (code "38") (name "/UGND") (class "Default")
      (node (ref "C20") (pin "1") (pinfunction "1_1") (pintype "passive"))
      (node (ref "ESD1") (pin "1") (pinfunction "GND_1") (pintype "bidirectional"))
      (node (ref "L1") (pin "2") (pinfunction "2_2") (pintype "passive"))
      (node (ref "U5") (pin "5") (pinfunction "UGND_5") (pintype "bidirectional"))
      (node (ref "U6") (pin "5") (pinfunction "UGND_5") (pintype "bidirectional"))
      (node (ref "USB1") (pin "5") (pinfunction "GND_5") (pintype "bidirectional"))
    )
    (net (code "39") (name "/VIN") (class "Default")
      (node (ref "D1") (pin "-") (pinfunction "-_-") (pintype "passive"))
      (node (ref "J1") (pin "VCC1") (pinfunction "+_VCC1") (pintype "bidirectional"))
      (node (ref "J1") (pin "VCC2") (pinfunction "+_VCC2") (pintype "bidirectional"))
      (node (ref "J1") (pin "VCC3") (pinfunction "+_VCC3") (pintype "bidirectional"))
      (node (ref "J1") (pin "VCC4") (pinfunction "+_VCC4") (pintype "bidirectional"))
      (node (ref "J2") (pin "8") (pinfunction "8_8") (pintype "bidirectional"))
      (node (ref "Q1") (pin "3") (pinfunction "D_3") (pintype "passive"))
    )
    (net (code "40") (name "/VUSB") (class "Default")
      (node (ref "F1") (pin "2") (pinfunction "2_2") (pintype "bidirectional"))
      (node (ref "Q2") (pin "3") (pinfunction "D_3") (pintype "passive"))
      (node (ref "U5") (pin "2") (pinfunction "UVCC_2") (pintype "bidirectional"))
      (node (ref "U5") (pin "7") (pinfunction "VBUS_7") (pintype "bidirectional"))
      (node (ref "U6") (pin "2") (pinfunction "UVCC_2") (pintype "bidirectional"))
      (node (ref "U6") (pin "7") (pinfunction "VBUS_7") (pintype "bidirectional"))
    )
    (net (code "41") (name "/XTAL1") (class "Default")
      (node (ref "C12") (pin "2") (pinfunction "2_2") (pintype "passive"))
      (node (ref "R12") (pin "2") (pinfunction "2_2") (pintype "passive"))
      (node (ref "U5") (pin "17") (pinfunction "XTAL1_17") (pintype "bidirectional"))
      (node (ref "U6") (pin "17") (pinfunction "XTAL1_17") (pintype "bidirectional"))
      (node (ref "X1") (pin "P$1") (pinfunction "P$1_P$1") (pintype "passive"))
    )
    (net (code "42") (name "/XTAL2") (class "Default")
      (node (ref "C13") (pin "2") (pinfunction "2_2") (pintype "passive"))
      (node (ref "R12") (pin "1") (pinfunction "1_1") (pintype "passive"))
      (node (ref "U5") (pin "16") (pinfunction "XTAL2_16") (pintype "bidirectional"))
      (node (ref "U6") (pin "16") (pinfunction "XTAL2_16") (pintype "bidirectional"))
      (node (ref "X1") (pin "P$3") (pinfunction "P$2_P$3") (pintype "passive"))
    )
    (net (code "43") (name "GND") (class "Default")
      (node (ref "C1") (pin "1") (pinfunction "1_1") (pintype "passive"))
      (node (ref "C10") (pin "1") (pinfunction "1_1") (pintype "passive"))
      (node (ref "C12") (pin "1") (pinfunction "1_1") (pintype "passive"))
      (node (ref "C13") (pin "1") (pinfunction "1_1") (pintype "passive"))
      (node (ref "C14") (pin "2") (pinfunction "2_2") (pintype "passive"))
      (node (ref "C15") (pin "2") (pinfunction "2_2") (pintype "passive"))
      (node (ref "C16") (pin "2") (pinfunction "2_2") (pintype "passive"))
      (node (ref "C17") (pin "2") (pinfunction "2_2") (pintype "passive"))
      (node (ref "C18") (pin "2") (pinfunction "2_2") (pintype "passive"))
      (node (ref "C19") (pin "2") (pinfunction "2_2") (pintype "passive"))
      (node (ref "C2") (pin "1") (pinfunction "1_1") (pintype "passive"))
      (node (ref "C21") (pin "2") (pinfunction "2_2") (pintype "passive"))
      (node (ref "C3") (pin "1") (pinfunction "1_1") (pintype "passive"))
      (node (ref "C4") (pin "1") (pinfunction "1_1") (pintype "passive"))
      (node (ref "C5") (pin "1") (pinfunction "1_1") (pintype "passive"))
      (node (ref "C6") (pin "1") (pinfunction "1_1") (pintype "passive"))
      (node (ref "C7") (pin "1") (pinfunction "1_1") (pintype "passive"))
      (node (ref "C9") (pin "1") (pinfunction "1_1") (pintype "passive"))
      (node (ref "D1") (pin "+") (pinfunction "+_+") (pintype "passive"))
      (node (ref "D3") (pin "-") (pinfunction "-_-") (pintype "passive"))
      (node (ref "D4") (pin "-") (pinfunction "-_-") (pintype "passive"))
      (node (ref "D6") (pin "-") (pinfunction "-_-") (pintype "passive"))
      (node (ref "J1") (pin "CDN1") (pinfunction "CDN_CDN1") (pintype "bidirectional"))
      (node (ref "J1") (pin "CDN2") (pinfunction "CDN_CDN2") (pintype "bidirectional"))
      (node (ref "J1") (pin "CDN3") (pinfunction "CDN_CDN3") (pintype "bidirectional"))
      (node (ref "J1") (pin "CDN4") (pinfunction "CDN_CDN4") (pintype "bidirectional"))
      (node (ref "J1") (pin "GND1") (pinfunction "-_GND1") (pintype "bidirectional"))
      (node (ref "J1") (pin "GND2") (pinfunction "-_GND2") (pintype "bidirectional"))
      (node (ref "J1") (pin "GND3") (pinfunction "-_GND3") (pintype "bidirectional"))
      (node (ref "J1") (pin "GND4") (pinfunction "-_GND4") (pintype "bidirectional"))
      (node (ref "J2") (pin "6") (pinfunction "6_6") (pintype "bidirectional"))
      (node (ref "J2") (pin "7") (pinfunction "7_7") (pintype "bidirectional"))
      (node (ref "J4") (pin "7") (pinfunction "7_7") (pintype "bidirectional"))
      (node (ref "J6") (pin "4") (pinfunction "4_4") (pintype "bidirectional"))
      (node (ref "J7") (pin "4") (pinfunction "4_4") (pintype "bidirectional"))
      (node (ref "J8") (pin "4") (pinfunction "4_4") (pintype "bidirectional"))
      (node (ref "L1") (pin "1") (pinfunction "1_1") (pintype "passive"))
      (node (ref "Q1") (pin "1") (pinfunction "G_1") (pintype "passive"))
      (node (ref "R20") (pin "1") (pinfunction "1_1") (pintype "passive"))
      (node (ref "R6") (pin "1") (pinfunction "1_1") (pintype "passive"))
      (node (ref "SW1") (pin "1") (pinfunction "1_1") (pintype "bidirectional"))
      (node (ref "U1") (pin "1") (pinfunction "GND_1") (pintype "bidirectional"))
      (node (ref "U2") (pin "4") (pinfunction "GND_4") (pintype "bidirectional"))
      (node (ref "U3") (pin "15") (pinfunction "GND_15") (pintype "bidirectional"))
      (node (ref "U4") (pin "4") (pinfunction "GND_4") (pintype "power_in"))
      (node (ref "U5") (pin "15") (pinfunction "GND_15") (pintype "bidirectional"))
      (node (ref "U5") (pin "23") (pinfunction "GND_23") (pintype "bidirectional"))
      (node (ref "U5") (pin "35") (pinfunction "GND_35") (pintype "bidirectional"))
      (node (ref "U5") (pin "43") (pinfunction "GND_43") (pintype "bidirectional"))
      (node (ref "U5") (pin "TAB") (pinfunction "GND_TAB") (pintype "bidirectional"))
      (node (ref "U6") (pin "15") (pinfunction "GND_15") (pintype "bidirectional"))
      (node (ref "U6") (pin "23") (pinfunction "GND_23") (pintype "bidirectional"))
      (node (ref "U6") (pin "35") (pinfunction "GND_35") (pintype "bidirectional"))
      (node (ref "U6") (pin "43") (pinfunction "GND_43") (pintype "bidirectional"))
      (node (ref "USB1") (pin "S1") (pinfunction "GND_S1") (pintype "bidirectional"))
      (node (ref "USB1") (pin "S2_1") (pinfunction "GND_S2_1") (pintype "bidirectional"))
      (node (ref "USB1") (pin "S2_2") (pinfunction "GND_S2_2") (pintype "bidirectional"))
      (node (ref "USB1") (pin "S2_3") (pinfunction "GND_S2_3") (pintype "bidirectional"))
      (node (ref "USB1") (pin "S3") (pinfunction "GND_S3") (pintype "bidirectional"))
      (node (ref "USB1") (pin "S4") (pinfunction "GND_S4") (pintype "bidirectional"))
      (node (ref "USB1") (pin "S5_1") (pinfunction "GND_S5_1") (pintype "bidirectional"))
      (node (ref "USB1") (pin "S5_2") (pinfunction "GND_S5_2") (pintype "bidirectional"))
      (node (ref "USB1") (pin "S5_3") (pinfunction "GND_S5_3") (pintype "bidirectional"))
      (node (ref "USB1") (pin "S6") (pinfunction "GND_S6") (pintype "bidirectional"))
      (node (ref "X1") (pin "P$2") (pinfunction "GND1_P$2") (pintype "power_in"))
      (node (ref "X1") (pin "P$4") (pinfunction "GND2_P$4") (pintype "power_in"))
    )
    (net (code "44") (name "Net-(C8-Pad2)") (class "Default")
      (node (ref "C8") (pin "2") (pinfunction "2_2") (pintype "passive"))
      (node (ref "R4") (pin "2") (pinfunction "2_2") (pintype "passive"))
    )
    (net (code "45") (name "Net-(C14-Pad1)") (class "Default")
      (node (ref "C14") (pin "1") (pinfunction "1_1") (pintype "passive"))
      (node (ref "R11") (pin "2") (pinfunction "2_2") (pintype "passive"))
    )
    (net (code "46") (name "Net-(D3-Pad+)") (class "Default")
      (node (ref "D3") (pin "+") (pinfunction "+_+") (pintype "passive"))
      (node (ref "R24") (pin "2") (pinfunction "2_2") (pintype "passive"))
    )
    (net (code "47") (name "Net-(D4-Pad+)") (class "Default")
      (node (ref "D4") (pin "+") (pinfunction "+_+") (pintype "passive"))
      (node (ref "D5") (pin "+") (pinfunction "+_+") (pintype "passive"))
      (node (ref "R25") (pin "2") (pinfunction "2_2") (pintype "passive"))
    )
    (net (code "48") (name "Net-(D6-Pad+)") (class "Default")
      (node (ref "D6") (pin "+") (pinfunction "+_+") (pintype "passive"))
      (node (ref "R26") (pin "2") (pinfunction "2_2") (pintype "passive"))
    )
    (net (code "49") (name "Net-(D7-Pad+)") (class "Default")
      (node (ref "D7") (pin "+") (pinfunction "+_+") (pintype "passive"))
      (node (ref "R28") (pin "2") (pinfunction "2_2") (pintype "passive"))
    )
    (net (code "50") (name "Net-(ESD1-IO1)") (class "Default")
      (node (ref "ESD1") (pin "2") (pinfunction "IO1_2") (pintype "bidirectional"))
      (node (ref "R3") (pin "1") (pinfunction "1_1") (pintype "passive"))
      (node (ref "USB1") (pin "3") (pinfunction "DP_3") (pintype "bidirectional"))
    )
    (net (code "51") (name "Net-(ESD1-IO2)") (class "Default")
      (node (ref "ESD1") (pin "3") (pinfunction "IO2_3") (pintype "bidirectional"))
      (node (ref "R2") (pin "1") (pinfunction "1_1") (pintype "passive"))
      (node (ref "USB1") (pin "2") (pinfunction "DM_2") (pintype "bidirectional"))
    )
    (net (code "52") (name "Net-(ESD1-VCC)") (class "Default")
      (node (ref "ESD1") (pin "4") (pinfunction "VCC_4") (pintype "bidirectional"))
      (node (ref "F1") (pin "1") (pinfunction "1_1") (pintype "bidirectional"))
      (node (ref "USB1") (pin "1") (pinfunction "VCC_1") (pintype "bidirectional"))
    )
    (net (code "53") (name "Net-(Q1-S)") (class "Default")
      (node (ref "C2") (pin "2") (pinfunction "2_2") (pintype "passive"))
      (node (ref "C3") (pin "2") (pinfunction "2_2") (pintype "passive"))
      (node (ref "Q1") (pin "2") (pinfunction "S_2") (pintype "passive"))
      (node (ref "R1") (pin "2") (pinfunction "2_2") (pintype "passive"))
      (node (ref "U2") (pin "2") (pinfunction "IN_2") (pintype "bidirectional"))
    )
    (net (code "54") (name "Net-(Q2-G)") (class "Default")
      (node (ref "Q2") (pin "1") (pinfunction "G_1") (pintype "passive"))
      (node (ref "R8") (pin "2") (pinfunction "2_2") (pintype "passive"))
    )
    (net (code "55") (name "Net-(R5-Pad2)") (class "Default")
      (node (ref "R5") (pin "2") (pinfunction "2_2") (pintype "passive"))
      (node (ref "R6") (pin "2") (pinfunction "2_2") (pintype "passive"))
      (node (ref "R7") (pin "1") (pinfunction "1_1") (pintype "passive"))
    )
    (net (code "56") (name "Net-(U2-BS)") (class "Default")
      (node (ref "R4") (pin "1") (pinfunction "1_1") (pintype "passive"))
      (node (ref "U2") (pin "5") (pinfunction "BS_5") (pintype "bidirectional"))
    )
    (net (code "57") (name "Net-(U2-EN{slash}SYNC)") (class "Default")
      (node (ref "R1") (pin "1") (pinfunction "1_1") (pintype "passive"))
      (node (ref "U2") (pin "6") (pinfunction "EN/SYNC_6") (pintype "bidirectional"))
    )
    (net (code "58") (name "Net-(U2-FB)") (class "Default")
      (node (ref "R5") (pin "1") (pinfunction "1_1") (pintype "passive"))
      (node (ref "U2") (pin "8") (pinfunction "FB_8") (pintype "bidirectional"))
    )
    (net (code "59") (name "Net-(U2-SS)") (class "Default")
      (node (ref "C7") (pin "2") (pinfunction "2_2") (pintype "passive"))
      (node (ref "U2") (pin "1") (pinfunction "SS_1") (pintype "bidirectional"))
    )
    (net (code "60") (name "Net-(U2-VCC)") (class "Default")
      (node (ref "C5") (pin "2") (pinfunction "2_2") (pintype "passive"))
      (node (ref "U2") (pin "7") (pinfunction "VCC_7") (pintype "bidirectional"))
    )
    (net (code "61") (name "Net-(U3-GPIO12)") (class "Default")
      (node (ref "R15") (pin "2") (pinfunction "2_2") (pintype "passive"))
      (node (ref "U3") (pin "6") (pinfunction "GPIO12_6") (pintype "bidirectional"))
    )
    (net (code "62") (name "Net-(U3-GPIO13)") (class "Default")
      (node (ref "R16") (pin "2") (pinfunction "2_2") (pintype "passive"))
      (node (ref "U3") (pin "7") (pinfunction "GPIO13_7") (pintype "bidirectional"))
    )
    (net (code "63") (name "Net-(U3-GPIO14)") (class "Default")
      (node (ref "R17") (pin "2") (pinfunction "2_2") (pintype "passive"))
      (node (ref "U3") (pin "5") (pinfunction "GPIO14_5") (pintype "bidirectional"))
    )
    (net (code "64") (name "Net-(U3-GPIO15)") (class "Default")
      (node (ref "R18") (pin "2") (pinfunction "2_2") (pintype "passive"))
      (node (ref "R20") (pin "2") (pinfunction "2_2") (pintype "passive"))
      (node (ref "U3") (pin "16") (pinfunction "GPIO15_16") (pintype "bidirectional"))
    )
    (net (code "65") (name "Net-(U3-GPIO16)") (class "Default")
      (node (ref "R19") (pin "2") (pinfunction "2_2") (pintype "passive"))
      (node (ref "U3") (pin "4") (pinfunction "GPIO16_4") (pintype "bidirectional"))
    )
    (net (code "66") (name "Net-(U3-RST)") (class "Default")
      (node (ref "R13") (pin "2") (pinfunction "2_2") (pintype "passive"))
      (node (ref "U3") (pin "1") (pinfunction "RST_1") (pintype "bidirectional"))
    )
    (net (code "67") (name "Net-(U3-RXD)") (class "Default")
      (node (ref "R22") (pin "1") (pinfunction "1_1") (pintype "passive"))
      (node (ref "U3") (pin "21") (pinfunction "RXD_21") (pintype "bidirectional"))
    )
    (net (code "68") (name "Net-(U3-TXD)") (class "Default")
      (node (ref "R21") (pin "1") (pinfunction "1_1") (pintype "passive"))
      (node (ref "U3") (pin "22") (pinfunction "TXD_22") (pintype "bidirectional"))
    )
    (net (code "69") (name "unconnected-(J2-Pad1)") (class "Default")
      (node (ref "J2") (pin "1") (pinfunction "1_1") (pintype "bidirectional"))
    )
    (net (code "70") (name "unconnected-(U3-ADC-Pad2)") (class "Default")
      (node (ref "U3") (pin "2") (pinfunction "ADC_2") (pintype "bidirectional"))
    )
    (net (code "71") (name "unconnected-(U3-CS0-Pad9)") (class "Default")
      (node (ref "U3") (pin "9") (pinfunction "CS0_9") (pintype "bidirectional"))
    )
    (net (code "72") (name "unconnected-(U3-IO9-Pad11)") (class "Default")
      (node (ref "U3") (pin "11") (pinfunction "IO9_11") (pintype "bidirectional"))
    )
    (net (code "73") (name "unconnected-(U3-IO10-Pad12)") (class "Default")
      (node (ref "U3") (pin "12") (pinfunction "IO10_12") (pintype "bidirectional"))
    )
    (net (code "74") (name "unconnected-(U3-MISO-Pad10)") (class "Default")
      (node (ref "U3") (pin "10") (pinfunction "MISO_10") (pintype "bidirectional"))
    )
    (net (code "75") (name "unconnected-(U3-MOSI-Pad13)") (class "Default")
      (node (ref "U3") (pin "13") (pinfunction "MOSI_13") (pintype "bidirectional"))
    )
    (net (code "76") (name "unconnected-(U3-SCLK-Pad14)") (class "Default")
      (node (ref "U3") (pin "14") (pinfunction "SCLK_14") (pintype "bidirectional"))
    )
    (net (code "77") (name "unconnected-(U4-NC1-Pad1)") (class "Default")
      (node (ref "U4") (pin "1") (pinfunction "NC1_1") (pintype "no_connect"))
    )
    (net (code "78") (name "unconnected-(U4-NC2-Pad2)") (class "Default")
      (node (ref "U4") (pin "2") (pinfunction "NC2_2") (pintype "no_connect"))
    )
    (net (code "79") (name "unconnected-(U4-NC3-Pad3)") (class "Default")
      (node (ref "U4") (pin "3") (pinfunction "NC3_3") (pintype "no_connect"))
    )
    (net (code "80") (name "unconnected-(U4-NC4-Pad7)") (class "Default")
      (node (ref "U4") (pin "7") (pinfunction "NC4_7") (pintype "no_connect"))
    )
    (net (code "81") (name "unconnected-(USB1-ID-Pad4)") (class "Default")
      (node (ref "USB1") (pin "4") (pinfunction "ID_4") (pintype "bidirectional"))
    )
  )
)
